# LEDPanel.net
KiCad netlist of a schematic drawn in EAGLE
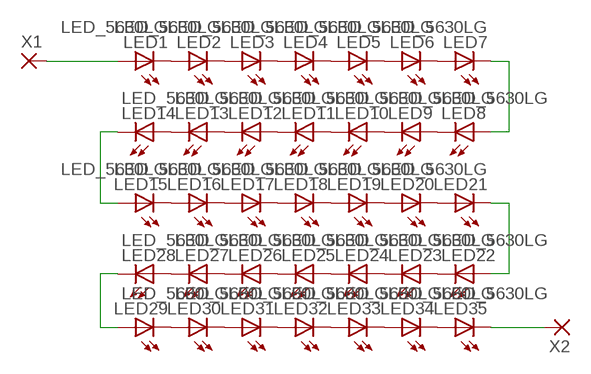
[diagram p0: schematic, sheet 1]

(export (version "E")
  (design (tool "Eeschema 10.0.6"))
  (components
    (comp (ref "LED1")
      (value "LED_5630LG")
      (footprint "eagle-import:LED5630_LG")
      (libsource (lib "eagle-import") (part "LED_5630LG"))
    )
    (comp (ref "LED2")
      (value "LED_5630LG")
      (footprint "eagle-import:LED5630_LG")
      (libsource (lib "eagle-import") (part "LED_5630LG"))
    )
    (comp (ref "LED3")
      (value "LED_5630LG")
      (footprint "eagle-import:LED5630_LG")
      (libsource (lib "eagle-import") (part "LED_5630LG"))
    )
    (comp (ref "LED4")
      (value "LED_5630LG")
      (footprint "eagle-import:LED5630_LG")
      (libsource (lib "eagle-import") (part "LED_5630LG"))
    )
    (comp (ref "LED5")
      (value "LED_5630LG")
      (footprint "eagle-import:LED5630_LG")
      (libsource (lib "eagle-import") (part "LED_5630LG"))
    )
    (comp (ref "LED6")
      (value "LED_5630LG")
      (footprint "eagle-import:LED5630_LG")
      (libsource (lib "eagle-import") (part "LED_5630LG"))
    )
    (comp (ref "LED7")
      (value "LED_5630LG")
      (footprint "eagle-import:LED5630_LG")
      (libsource (lib "eagle-import") (part "LED_5630LG"))
    )
    (comp (ref "LED8")
      (value "LED_5630LG")
      (footprint "eagle-import:LED5630_LG")
      (libsource (lib "eagle-import") (part "LED_5630LG"))
    )
    (comp (ref "LED9")
      (value "LED_5630LG")
      (footprint "eagle-import:LED5630_LG")
      (libsource (lib "eagle-import") (part "LED_5630LG"))
    )
    (comp (ref "LED10")
      (value "LED_5630LG")
      (footprint "eagle-import:LED5630_LG")
      (libsource (lib "eagle-import") (part "LED_5630LG"))
    )
    (comp (ref "LED11")
      (value "LED_5630LG")
      (footprint "eagle-import:LED5630_LG")
      (libsource (lib "eagle-import") (part "LED_5630LG"))
    )
    (comp (ref "LED12")
      (value "LED_5630LG")
      (footprint "eagle-import:LED5630_LG")
      (libsource (lib "eagle-import") (part "LED_5630LG"))
    )
    (comp (ref "LED13")
      (value "LED_5630LG")
      (footprint "eagle-import:LED5630_LG")
      (libsource (lib "eagle-import") (part "LED_5630LG"))
    )
    (comp (ref "LED14")
      (value "LED_5630LG")
      (footprint "eagle-import:LED5630_LG")
      (libsource (lib "eagle-import") (part "LED_5630LG"))
    )
    (comp (ref "LED15")
      (value "LED_5630LG")
      (footprint "eagle-import:LED5630_LG")
      (libsource (lib "eagle-import") (part "LED_5630LG"))
    )
    (comp (ref "LED16")
      (value "LED_5630LG")
      (footprint "eagle-import:LED5630_LG")
      (libsource (lib "eagle-import") (part "LED_5630LG"))
    )
    (comp (ref "LED17")
      (value "LED_5630LG")
      (footprint "eagle-import:LED5630_LG")
      (libsource (lib "eagle-import") (part "LED_5630LG"))
    )
    (comp (ref "LED18")
      (value "LED_5630LG")
      (footprint "eagle-import:LED5630_LG")
      (libsource (lib "eagle-import") (part "LED_5630LG"))
    )
    (comp (ref "LED19")
      (value "LED_5630LG")
      (footprint "eagle-import:LED5630_LG")
      (libsource (lib "eagle-import") (part "LED_5630LG"))
    )
    (comp (ref "LED20")
      (value "LED_5630LG")
      (footprint "eagle-import:LED5630_LG")
      (libsource (lib "eagle-import") (part "LED_5630LG"))
    )
    (comp (ref "LED21")
      (value "LED_5630LG")
      (footprint "eagle-import:LED5630_LG")
      (libsource (lib "eagle-import") (part "LED_5630LG"))
    )
    (comp (ref "LED22")
      (value "LED_5630LG")
      (footprint "eagle-import:LED5630_LG")
      (libsource (lib "eagle-import") (part "LED_5630LG"))
    )
    (comp (ref "LED23")
      (value "LED_5630LG")
      (footprint "eagle-import:LED5630_LG")
      (libsource (lib "eagle-import") (part "LED_5630LG"))
    )
    (comp (ref "LED24")
      (value "LED_5630LG")
      (footprint "eagle-import:LED5630_LG")
      (libsource (lib "eagle-import") (part "LED_5630LG"))
    )
    (comp (ref "LED25")
      (value "LED_5630LG")
      (footprint "eagle-import:LED5630_LG")
      (libsource (lib "eagle-import") (part "LED_5630LG"))
    )
    (comp (ref "LED26")
      (value "LED_5630LG")
      (footprint "eagle-import:LED5630_LG")
      (libsource (lib "eagle-import") (part "LED_5630LG"))
    )
    (comp (ref "LED27")
      (value "LED_5630LG")
      (footprint "eagle-import:LED5630_LG")
      (libsource (lib "eagle-import") (part "LED_5630LG"))
    )
    (comp (ref "LED28")
      (value "LED_5630LG")
      (footprint "eagle-import:LED5630_LG")
      (libsource (lib "eagle-import") (part "LED_5630LG"))
    )
    (comp (ref "LED29")
      (value "LED_5630LG")
      (footprint "eagle-import:LED5630_LG")
      (libsource (lib "eagle-import") (part "LED_5630LG"))
    )
    (comp (ref "LED30")
      (value "LED_5630LG")
      (footprint "eagle-import:LED5630_LG")
      (libsource (lib "eagle-import") (part "LED_5630LG"))
    )
    (comp (ref "LED31")
      (value "LED_5630LG")
      (footprint "eagle-import:LED5630_LG")
      (libsource (lib "eagle-import") (part "LED_5630LG"))
    )
    (comp (ref "LED32")
      (value "LED_5630LG")
      (footprint "eagle-import:LED5630_LG")
      (libsource (lib "eagle-import") (part "LED_5630LG"))
    )
    (comp (ref "LED33")
      (value "LED_5630LG")
      (footprint "eagle-import:LED5630_LG")
      (libsource (lib "eagle-import") (part "LED_5630LG"))
    )
    (comp (ref "LED34")
      (value "LED_5630LG")
      (footprint "eagle-import:LED5630_LG")
      (libsource (lib "eagle-import") (part "LED_5630LG"))
    )
    (comp (ref "LED35")
      (value "LED_5630LG")
      (footprint "eagle-import:LED5630_LG")
      (libsource (lib "eagle-import") (part "LED_5630LG"))
    )
    (comp (ref "X1")
      (value "WIREPAD-SMD2")
      (footprint "eagle-import:PAD-1.27X2.54")
      (libsource (lib "eagle-import") (part "WIREPAD-SMD2"))
    )
    (comp (ref "X2")
      (value "WIREPAD-SMD2")
      (footprint "eagle-import:PAD-1.27X2.54")
      (libsource (lib "eagle-import") (part "WIREPAD-SMD2"))
    )
  )
  (nets
    (net (code "1") (name "Net-(LED1-C-PadC-NC)") (class "Default")
      (node (ref "LED1") (pin "C-NC") (pinfunction "C_C-NC") (pintype "passive"))
      (node (ref "LED1") (pin "C1") (pinfunction "C_C1") (pintype "passive"))
      (node (ref "LED2") (pin "A-TAB") (pinfunction "A_A-TAB") (pintype "passive"))
      (node (ref "LED2") (pin "A1") (pinfunction "A_A1") (pintype "passive"))
      (node (ref "LED2") (pin "A2") (pinfunction "A_A2") (pintype "passive"))
    )
    (net (code "2") (name "Net-(LED2-C-PadC-NC)") (class "Default")
      (node (ref "LED2") (pin "C-NC") (pinfunction "C_C-NC") (pintype "passive"))
      (node (ref "LED2") (pin "C1") (pinfunction "C_C1") (pintype "passive"))
      (node (ref "LED3") (pin "A-TAB") (pinfunction "A_A-TAB") (pintype "passive"))
      (node (ref "LED3") (pin "A1") (pinfunction "A_A1") (pintype "passive"))
      (node (ref "LED3") (pin "A2") (pinfunction "A_A2") (pintype "passive"))
    )
    (net (code "3") (name "Net-(LED3-C-PadC-NC)") (class "Default")
      (node (ref "LED3") (pin "C-NC") (pinfunction "C_C-NC") (pintype "passive"))
      (node (ref "LED3") (pin "C1") (pinfunction "C_C1") (pintype "passive"))
      (node (ref "LED4") (pin "A-TAB") (pinfunction "A_A-TAB") (pintype "passive"))
      (node (ref "LED4") (pin "A1") (pinfunction "A_A1") (pintype "passive"))
      (node (ref "LED4") (pin "A2") (pinfunction "A_A2") (pintype "passive"))
    )
    (net (code "4") (name "Net-(LED4-C-PadC-NC)") (class "Default")
      (node (ref "LED4") (pin "C-NC") (pinfunction "C_C-NC") (pintype "passive"))
      (node (ref "LED4") (pin "C1") (pinfunction "C_C1") (pintype "passive"))
      (node (ref "LED5") (pin "A-TAB") (pinfunction "A_A-TAB") (pintype "passive"))
      (node (ref "LED5") (pin "A1") (pinfunction "A_A1") (pintype "passive"))
      (node (ref "LED5") (pin "A2") (pinfunction "A_A2") (pintype "passive"))
    )
    (net (code "5") (name "Net-(LED5-C-PadC-NC)") (class "Default")
      (node (ref "LED5") (pin "C-NC") (pinfunction "C_C-NC") (pintype "passive"))
      (node (ref "LED5") (pin "C1") (pinfunction "C_C1") (pintype "passive"))
      (node (ref "LED6") (pin "A-TAB") (pinfunction "A_A-TAB") (pintype "passive"))
      (node (ref "LED6") (pin "A1") (pinfunction "A_A1") (pintype "passive"))
      (node (ref "LED6") (pin "A2") (pinfunction "A_A2") (pintype "passive"))
    )
    (net (code "6") (name "Net-(LED6-C-PadC-NC)") (class "Default")
      (node (ref "LED6") (pin "C-NC") (pinfunction "C_C-NC") (pintype "passive"))
      (node (ref "LED6") (pin "C1") (pinfunction "C_C1") (pintype "passive"))
      (node (ref "LED7") (pin "A-TAB") (pinfunction "A_A-TAB") (pintype "passive"))
      (node (ref "LED7") (pin "A1") (pinfunction "A_A1") (pintype "passive"))
      (node (ref "LED7") (pin "A2") (pinfunction "A_A2") (pintype "passive"))
    )
    (net (code "7") (name "Net-(LED7-C-PadC-NC)") (class "Default")
      (node (ref "LED7") (pin "C-NC") (pinfunction "C_C-NC") (pintype "passive"))
      (node (ref "LED7") (pin "C1") (pinfunction "C_C1") (pintype "passive"))
      (node (ref "LED8") (pin "A-TAB") (pinfunction "A_A-TAB") (pintype "passive"))
      (node (ref "LED8") (pin "A1") (pinfunction "A_A1") (pintype "passive"))
      (node (ref "LED8") (pin "A2") (pinfunction "A_A2") (pintype "passive"))
    )
    (net (code "8") (name "Net-(LED8-C-PadC-NC)") (class "Default")
      (node (ref "LED8") (pin "C-NC") (pinfunction "C_C-NC") (pintype "passive"))
      (node (ref "LED8") (pin "C1") (pinfunction "C_C1") (pintype "passive"))
      (node (ref "LED9") (pin "A-TAB") (pinfunction "A_A-TAB") (pintype "passive"))
      (node (ref "LED9") (pin "A1") (pinfunction "A_A1") (pintype "passive"))
      (node (ref "LED9") (pin "A2") (pinfunction "A_A2") (pintype "passive"))
    )
    (net (code "9") (name "Net-(LED10-A-PadA-TAB)") (class "Default")
      (node (ref "LED10") (pin "A-TAB") (pinfunction "A_A-TAB") (pintype "passive"))
      (node (ref "LED10") (pin "A1") (pinfunction "A_A1") (pintype "passive"))
      (node (ref "LED10") (pin "A2") (pinfunction "A_A2") (pintype "passive"))
      (node (ref "LED9") (pin "C-NC") (pinfunction "C_C-NC") (pintype "passive"))
      (node (ref "LED9") (pin "C1") (pinfunction "C_C1") (pintype "passive"))
    )
    (net (code "10") (name "Net-(LED10-C-PadC-NC)") (class "Default")
      (node (ref "LED10") (pin "C-NC") (pinfunction "C_C-NC") (pintype "passive"))
      (node (ref "LED10") (pin "C1") (pinfunction "C_C1") (pintype "passive"))
      (node (ref "LED11") (pin "A-TAB") (pinfunction "A_A-TAB") (pintype "passive"))
      (node (ref "LED11") (pin "A1") (pinfunction "A_A1") (pintype "passive"))
      (node (ref "LED11") (pin "A2") (pinfunction "A_A2") (pintype "passive"))
    )
    (net (code "11") (name "Net-(LED11-C-PadC-NC)") (class "Default")
      (node (ref "LED11") (pin "C-NC") (pinfunction "C_C-NC") (pintype "passive"))
      (node (ref "LED11") (pin "C1") (pinfunction "C_C1") (pintype "passive"))
      (node (ref "LED12") (pin "A-TAB") (pinfunction "A_A-TAB") (pintype "passive"))
      (node (ref "LED12") (pin "A1") (pinfunction "A_A1") (pintype "passive"))
      (node (ref "LED12") (pin "A2") (pinfunction "A_A2") (pintype "passive"))
    )
    (net (code "12") (name "Net-(LED12-C-PadC-NC)") (class "Default")
      (node (ref "LED12") (pin "C-NC") (pinfunction "C_C-NC") (pintype "passive"))
      (node (ref "LED12") (pin "C1") (pinfunction "C_C1") (pintype "passive"))
      (node (ref "LED13") (pin "A-TAB") (pinfunction "A_A-TAB") (pintype "passive"))
      (node (ref "LED13") (pin "A1") (pinfunction "A_A1") (pintype "passive"))
      (node (ref "LED13") (pin "A2") (pinfunction "A_A2") (pintype "passive"))
    )
    (net (code "13") (name "Net-(LED13-C-PadC-NC)") (class "Default")
      (node (ref "LED13") (pin "C-NC") (pinfunction "C_C-NC") (pintype "passive"))
      (node (ref "LED13") (pin "C1") (pinfunction "C_C1") (pintype "passive"))
      (node (ref "LED14") (pin "A-TAB") (pinfunction "A_A-TAB") (pintype "passive"))
      (node (ref "LED14") (pin "A1") (pinfunction "A_A1") (pintype "passive"))
      (node (ref "LED14") (pin "A2") (pinfunction "A_A2") (pintype "passive"))
    )
    (net (code "14") (name "Net-(LED14-C-PadC-NC)") (class "Default")
      (node (ref "LED14") (pin "C-NC") (pinfunction "C_C-NC") (pintype "passive"))
      (node (ref "LED14") (pin "C1") (pinfunction "C_C1") (pintype "passive"))
      (node (ref "LED15") (pin "A-TAB") (pinfunction "A_A-TAB") (pintype "passive"))
      (node (ref "LED15") (pin "A1") (pinfunction "A_A1") (pintype "passive"))
      (node (ref "LED15") (pin "A2") (pinfunction "A_A2") (pintype "passive"))
    )
    (net (code "15") (name "Net-(LED15-C-PadC-NC)") (class "Default")
      (node (ref "LED15") (pin "C-NC") (pinfunction "C_C-NC") (pintype "passive"))
      (node (ref "LED15") (pin "C1") (pinfunction "C_C1") (pintype "passive"))
      (node (ref "LED16") (pin "A-TAB") (pinfunction "A_A-TAB") (pintype "passive"))
      (node (ref "LED16") (pin "A1") (pinfunction "A_A1") (pintype "passive"))
      (node (ref "LED16") (pin "A2") (pinfunction "A_A2") (pintype "passive"))
    )
    (net (code "16") (name "Net-(LED16-C-PadC-NC)") (class "Default")
      (node (ref "LED16") (pin "C-NC") (pinfunction "C_C-NC") (pintype "passive"))
      (node (ref "LED16") (pin "C1") (pinfunction "C_C1") (pintype "passive"))
      (node (ref "LED17") (pin "A-TAB") (pinfunction "A_A-TAB") (pintype "passive"))
      (node (ref "LED17") (pin "A1") (pinfunction "A_A1") (pintype "passive"))
      (node (ref "LED17") (pin "A2") (pinfunction "A_A2") (pintype "passive"))
    )
    (net (code "17") (name "Net-(LED17-C-PadC-NC)") (class "Default")
      (node (ref "LED17") (pin "C-NC") (pinfunction "C_C-NC") (pintype "passive"))
      (node (ref "LED17") (pin "C1") (pinfunction "C_C1") (pintype "passive"))
      (node (ref "LED18") (pin "A-TAB") (pinfunction "A_A-TAB") (pintype "passive"))
      (node (ref "LED18") (pin "A1") (pinfunction "A_A1") (pintype "passive"))
      (node (ref "LED18") (pin "A2") (pinfunction "A_A2") (pintype "passive"))
    )
    (net (code "18") (name "Net-(LED18-C-PadC-NC)") (class "Default")
      (node (ref "LED18") (pin "C-NC") (pinfunction "C_C-NC") (pintype "passive"))
      (node (ref "LED18") (pin "C1") (pinfunction "C_C1") (pintype "passive"))
      (node (ref "LED19") (pin "A-TAB") (pinfunction "A_A-TAB") (pintype "passive"))
      (node (ref "LED19") (pin "A1") (pinfunction "A_A1") (pintype "passive"))
      (node (ref "LED19") (pin "A2") (pinfunction "A_A2") (pintype "passive"))
    )
    (net (code "19") (name "Net-(LED19-C-PadC-NC)") (class "Default")
      (node (ref "LED19") (pin "C-NC") (pinfunction "C_C-NC") (pintype "passive"))
      (node (ref "LED19") (pin "C1") (pinfunction "C_C1") (pintype "passive"))
      (node (ref "LED20") (pin "A-TAB") (pinfunction "A_A-TAB") (pintype "passive"))
      (node (ref "LED20") (pin "A1") (pinfunction "A_A1") (pintype "passive"))
      (node (ref "LED20") (pin "A2") (pinfunction "A_A2") (pintype "passive"))
    )
    (net (code "20") (name "Net-(LED20-C-PadC-NC)") (class "Default")
      (node (ref "LED20") (pin "C-NC") (pinfunction "C_C-NC") (pintype "passive"))
      (node (ref "LED20") (pin "C1") (pinfunction "C_C1") (pintype "passive"))
      (node (ref "LED21") (pin "A-TAB") (pinfunction "A_A-TAB") (pintype "passive"))
      (node (ref "LED21") (pin "A1") (pinfunction "A_A1") (pintype "passive"))
      (node (ref "LED21") (pin "A2") (pinfunction "A_A2") (pintype "passive"))
    )
    (net (code "21") (name "Net-(LED21-C-PadC-NC)") (class "Default")
      (node (ref "LED21") (pin "C-NC") (pinfunction "C_C-NC") (pintype "passive"))
      (node (ref "LED21") (pin "C1") (pinfunction "C_C1") (pintype "passive"))
      (node (ref "LED22") (pin "A-TAB") (pinfunction "A_A-TAB") (pintype "passive"))
      (node (ref "LED22") (pin "A1") (pinfunction "A_A1") (pintype "passive"))
      (node (ref "LED22") (pin "A2") (pinfunction "A_A2") (pintype "passive"))
    )
    (net (code "22") (name "Net-(LED22-C-PadC-NC)") (class "Default")
      (node (ref "LED22") (pin "C-NC") (pinfunction "C_C-NC") (pintype "passive"))
      (node (ref "LED22") (pin "C1") (pinfunction "C_C1") (pintype "passive"))
      (node (ref "LED23") (pin "A-TAB") (pinfunction "A_A-TAB") (pintype "passive"))
      (node (ref "LED23") (pin "A1") (pinfunction "A_A1") (pintype "passive"))
      (node (ref "LED23") (pin "A2") (pinfunction "A_A2") (pintype "passive"))
    )
    (net (code "23") (name "Net-(LED23-C-PadC-NC)") (class "Default")
      (node (ref "LED23") (pin "C-NC") (pinfunction "C_C-NC") (pintype "passive"))
      (node (ref "LED23") (pin "C1") (pinfunction "C_C1") (pintype "passive"))
      (node (ref "LED24") (pin "A-TAB") (pinfunction "A_A-TAB") (pintype "passive"))
      (node (ref "LED24") (pin "A1") (pinfunction "A_A1") (pintype "passive"))
      (node (ref "LED24") (pin "A2") (pinfunction "A_A2") (pintype "passive"))
    )
    (net (code "24") (name "Net-(LED24-C-PadC-NC)") (class "Default")
      (node (ref "LED24") (pin "C-NC") (pinfunction "C_C-NC") (pintype "passive"))
      (node (ref "LED24") (pin "C1") (pinfunction "C_C1") (pintype "passive"))
      (node (ref "LED25") (pin "A-TAB") (pinfunction "A_A-TAB") (pintype "passive"))
      (node (ref "LED25") (pin "A1") (pinfunction "A_A1") (pintype "passive"))
      (node (ref "LED25") (pin "A2") (pinfunction "A_A2") (pintype "passive"))
    )
    (net (code "25") (name "Net-(LED25-C-PadC-NC)") (class "Default")
      (node (ref "LED25") (pin "C-NC") (pinfunction "C_C-NC") (pintype "passive"))
      (node (ref "LED25") (pin "C1") (pinfunction "C_C1") (pintype "passive"))
      (node (ref "LED26") (pin "A-TAB") (pinfunction "A_A-TAB") (pintype "passive"))
      (node (ref "LED26") (pin "A1") (pinfunction "A_A1") (pintype "passive"))
      (node (ref "LED26") (pin "A2") (pinfunction "A_A2") (pintype "passive"))
    )
    (net (code "26") (name "Net-(LED26-C-PadC-NC)") (class "Default")
      (node (ref "LED26") (pin "C-NC") (pinfunction "C_C-NC") (pintype "passive"))
      (node (ref "LED26") (pin "C1") (pinfunction "C_C1") (pintype "passive"))
      (node (ref "LED27") (pin "A-TAB") (pinfunction "A_A-TAB") (pintype "passive"))
      (node (ref "LED27") (pin "A1") (pinfunction "A_A1") (pintype "passive"))
      (node (ref "LED27") (pin "A2") (pinfunction "A_A2") (pintype "passive"))
    )
    (net (code "27") (name "Net-(LED27-C-PadC-NC)") (class "Default")
      (node (ref "LED27") (pin "C-NC") (pinfunction "C_C-NC") (pintype "passive"))
      (node (ref "LED27") (pin "C1") (pinfunction "C_C1") (pintype "passive"))
      (node (ref "LED28") (pin "A-TAB") (pinfunction "A_A-TAB") (pintype "passive"))
      (node (ref "LED28") (pin "A1") (pinfunction "A_A1") (pintype "passive"))
      (node (ref "LED28") (pin "A2") (pinfunction "A_A2") (pintype "passive"))
    )
    (net (code "28") (name "Net-(LED28-C-PadC-NC)") (class "Default")
      (node (ref "LED28") (pin "C-NC") (pinfunction "C_C-NC") (pintype "passive"))
      (node (ref "LED28") (pin "C1") (pinfunction "C_C1") (pintype "passive"))
      (node (ref "LED29") (pin "A-TAB") (pinfunction "A_A-TAB") (pintype "passive"))
      (node (ref "LED29") (pin "A1") (pinfunction "A_A1") (pintype "passive"))
      (node (ref "LED29") (pin "A2") (pinfunction "A_A2") (pintype "passive"))
    )
    (net (code "29") (name "Net-(LED29-C-PadC-NC)") (class "Default")
      (node (ref "LED29") (pin "C-NC") (pinfunction "C_C-NC") (pintype "passive"))
      (node (ref "LED29") (pin "C1") (pinfunction "C_C1") (pintype "passive"))
      (node (ref "LED30") (pin "A-TAB") (pinfunction "A_A-TAB") (pintype "passive"))
      (node (ref "LED30") (pin "A1") (pinfunction "A_A1") (pintype "passive"))
      (node (ref "LED30") (pin "A2") (pinfunction "A_A2") (pintype "passive"))
    )
    (net (code "30") (name "Net-(LED30-C-PadC-NC)") (class "Default")
      (node (ref "LED30") (pin "C-NC") (pinfunction "C_C-NC") (pintype "passive"))
      (node (ref "LED30") (pin "C1") (pinfunction "C_C1") (pintype "passive"))
      (node (ref "LED31") (pin "A-TAB") (pinfunction "A_A-TAB") (pintype "passive"))
      (node (ref "LED31") (pin "A1") (pinfunction "A_A1") (pintype "passive"))
      (node (ref "LED31") (pin "A2") (pinfunction "A_A2") (pintype "passive"))
    )
    (net (code "31") (name "Net-(LED31-C-PadC-NC)") (class "Default")
      (node (ref "LED31") (pin "C-NC") (pinfunction "C_C-NC") (pintype "passive"))
      (node (ref "LED31") (pin "C1") (pinfunction "C_C1") (pintype "passive"))
      (node (ref "LED32") (pin "A-TAB") (pinfunction "A_A-TAB") (pintype "passive"))
      (node (ref "LED32") (pin "A1") (pinfunction "A_A1") (pintype "passive"))
      (node (ref "LED32") (pin "A2") (pinfunction "A_A2") (pintype "passive"))
    )
    (net (code "32") (name "Net-(LED32-C-PadC-NC)") (class "Default")
      (node (ref "LED32") (pin "C-NC") (pinfunction "C_C-NC") (pintype "passive"))
      (node (ref "LED32") (pin "C1") (pinfunction "C_C1") (pintype "passive"))
      (node (ref "LED33") (pin "A-TAB") (pinfunction "A_A-TAB") (pintype "passive"))
      (node (ref "LED33") (pin "A1") (pinfunction "A_A1") (pintype "passive"))
      (node (ref "LED33") (pin "A2") (pinfunction "A_A2") (pintype "passive"))
    )
    (net (code "33") (name "Net-(LED33-C-PadC-NC)") (class "Default")
      (node (ref "LED33") (pin "C-NC") (pinfunction "C_C-NC") (pintype "passive"))
      (node (ref "LED33") (pin "C1") (pinfunction "C_C1") (pintype "passive"))
      (node (ref "LED34") (pin "A-TAB") (pinfunction "A_A-TAB") (pintype "passive"))
      (node (ref "LED34") (pin "A1") (pinfunction "A_A1") (pintype "passive"))
      (node (ref "LED34") (pin "A2") (pinfunction "A_A2") (pintype "passive"))
    )
    (net (code "34") (name "Net-(LED34-C-PadC-NC)") (class "Default")
      (node (ref "LED34") (pin "C-NC") (pinfunction "C_C-NC") (pintype "passive"))
      (node (ref "LED34") (pin "C1") (pinfunction "C_C1") (pintype "passive"))
      (node (ref "LED35") (pin "A-TAB") (pinfunction "A_A-TAB") (pintype "passive"))
      (node (ref "LED35") (pin "A1") (pinfunction "A_A1") (pintype "passive"))
      (node (ref "LED35") (pin "A2") (pinfunction "A_A2") (pintype "passive"))
    )
    (net (code "35") (name "Net-(X1-P)") (class "Default")
      (node (ref "LED1") (pin "A-TAB") (pinfunction "A_A-TAB") (pintype "passive"))
      (node (ref "LED1") (pin "A1") (pinfunction "A_A1") (pintype "passive"))
      (node (ref "LED1") (pin "A2") (pinfunction "A_A2") (pintype "passive"))
      (node (ref "X1") (pin "P$1") (pinfunction "P_P$1") (pintype "passive"))
    )
    (net (code "36") (name "Net-(X2-P)") (class "Default")
      (node (ref "LED35") (pin "C-NC") (pinfunction "C_C-NC") (pintype "passive"))
      (node (ref "LED35") (pin "C1") (pinfunction "C_C1") (pintype "passive"))
      (node (ref "X2") (pin "P$1") (pinfunction "P_P$1") (pintype "passive"))
    )
  )
)
